# mrShark_09.net
KiCad netlist of a schematic drawn in EAGLE
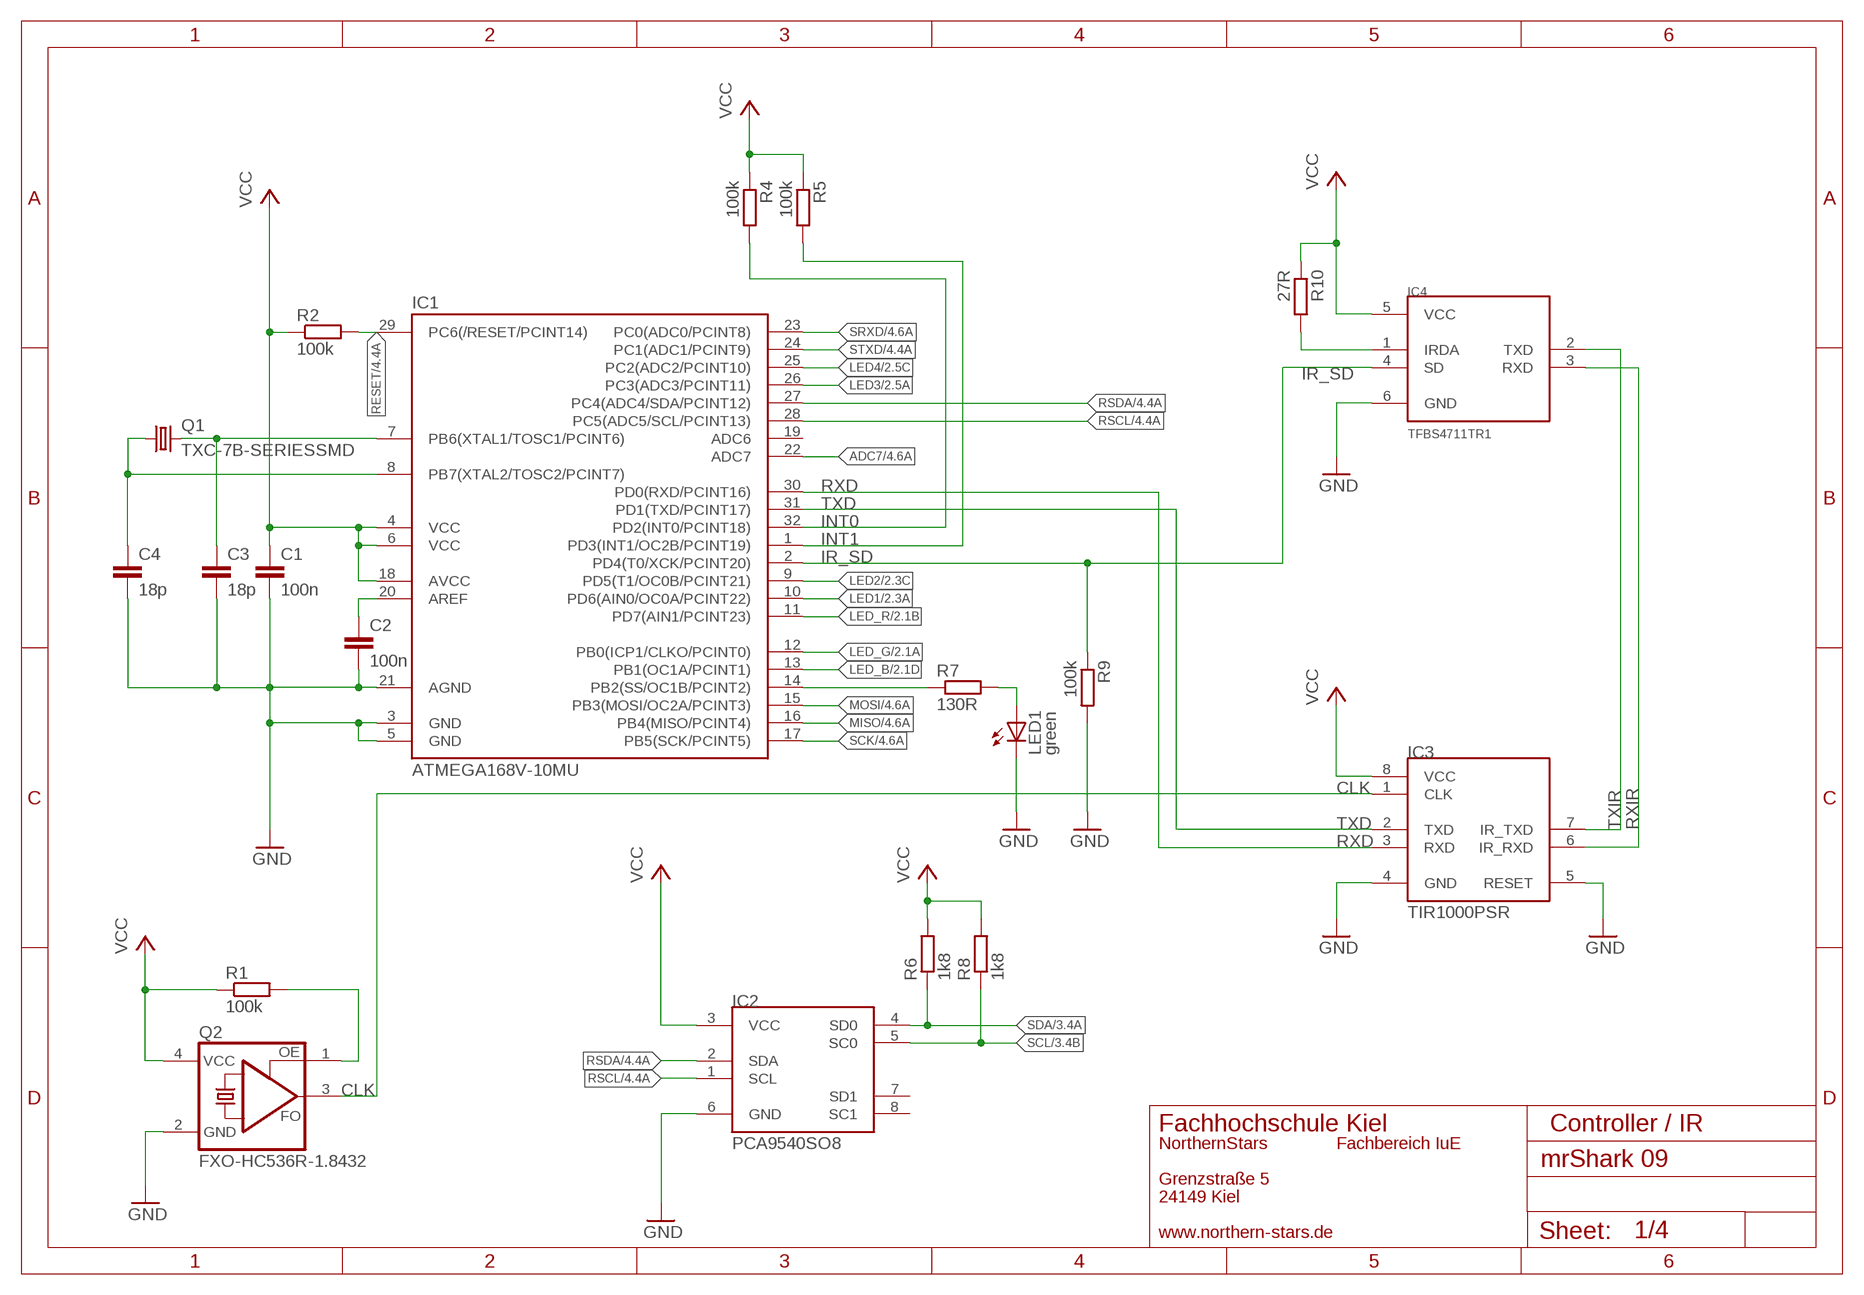
[diagram p0: schematic, sheet 1]
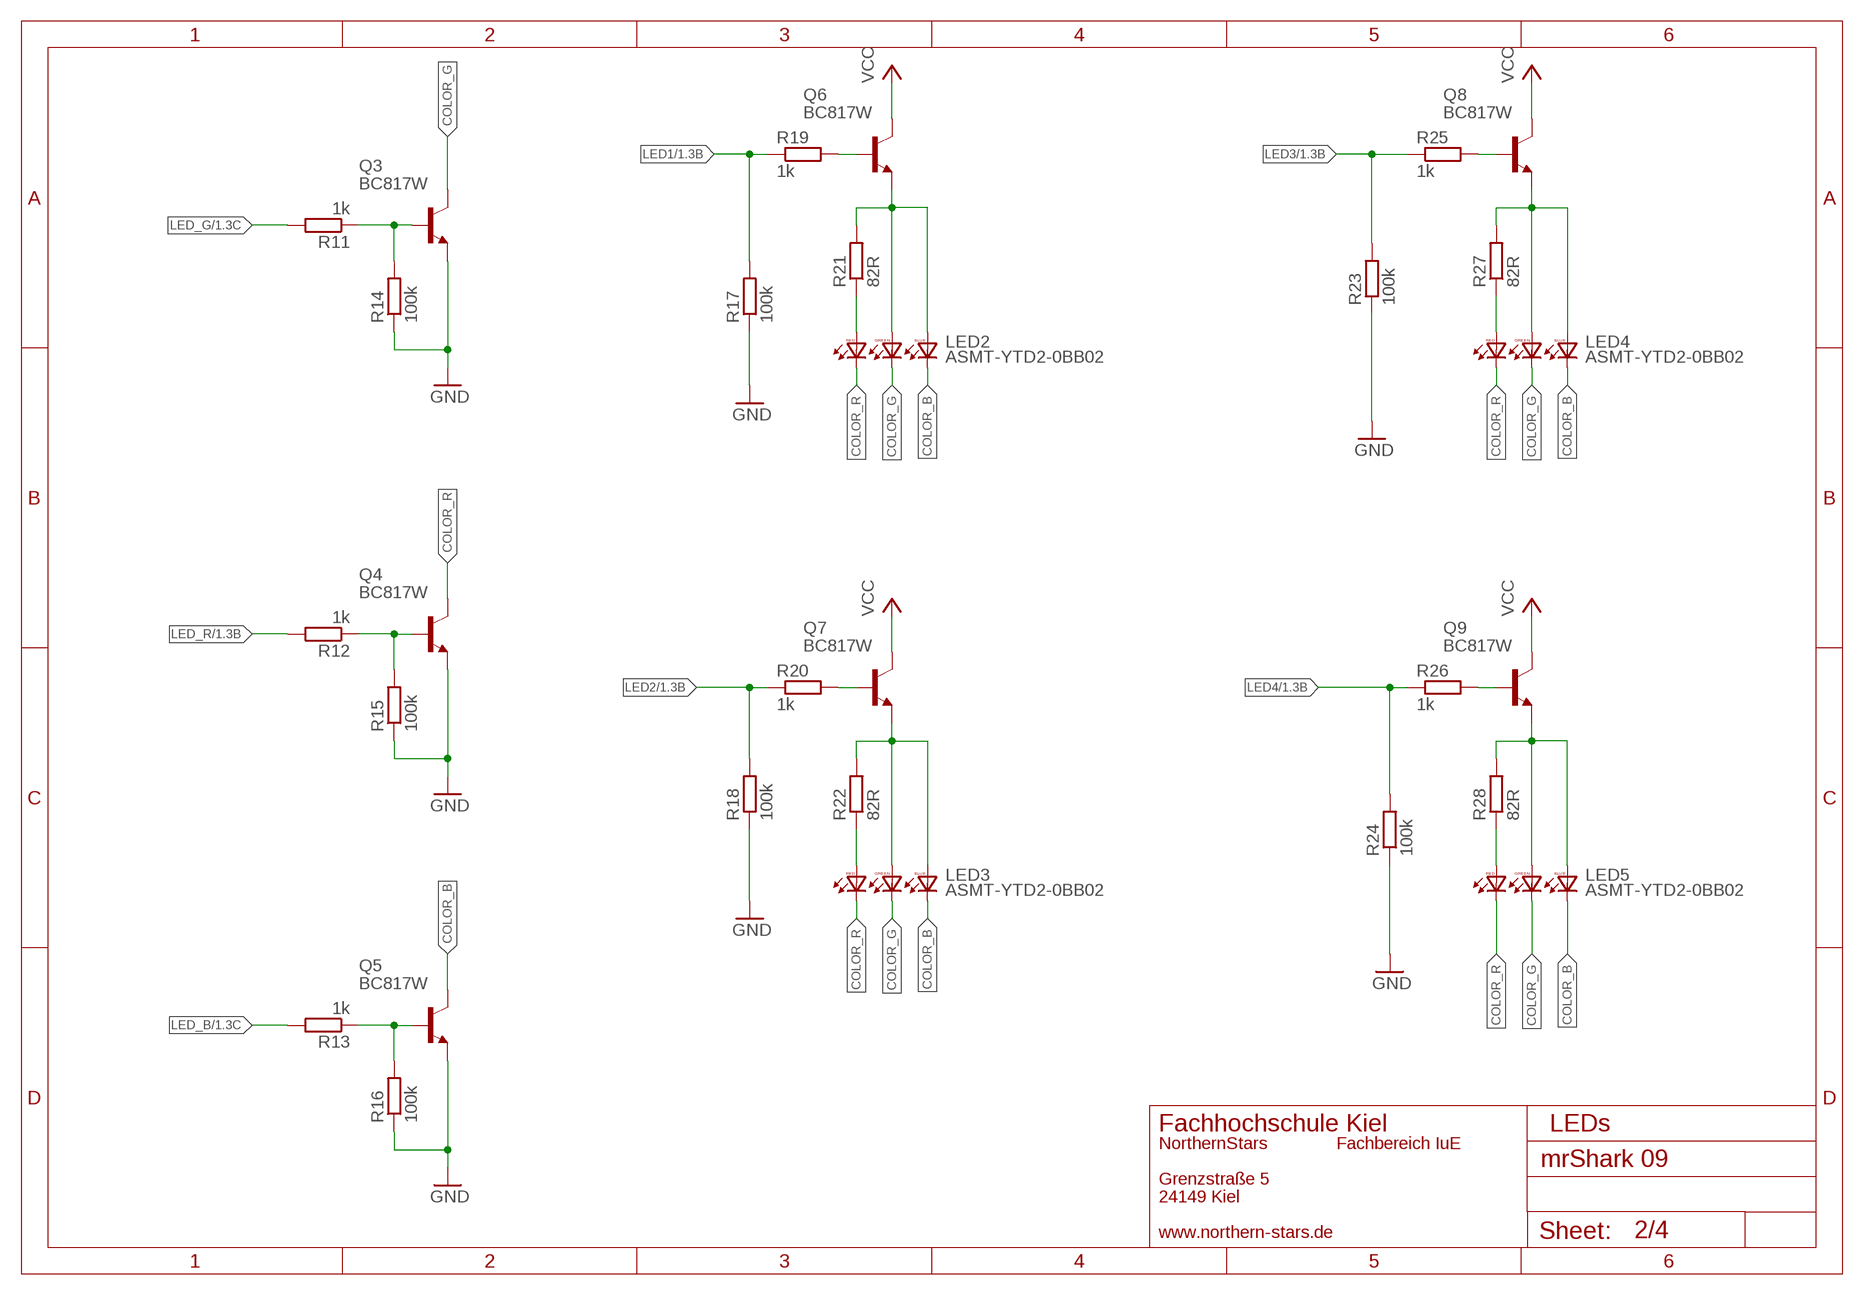
[diagram p1: schematic, sheet 2]
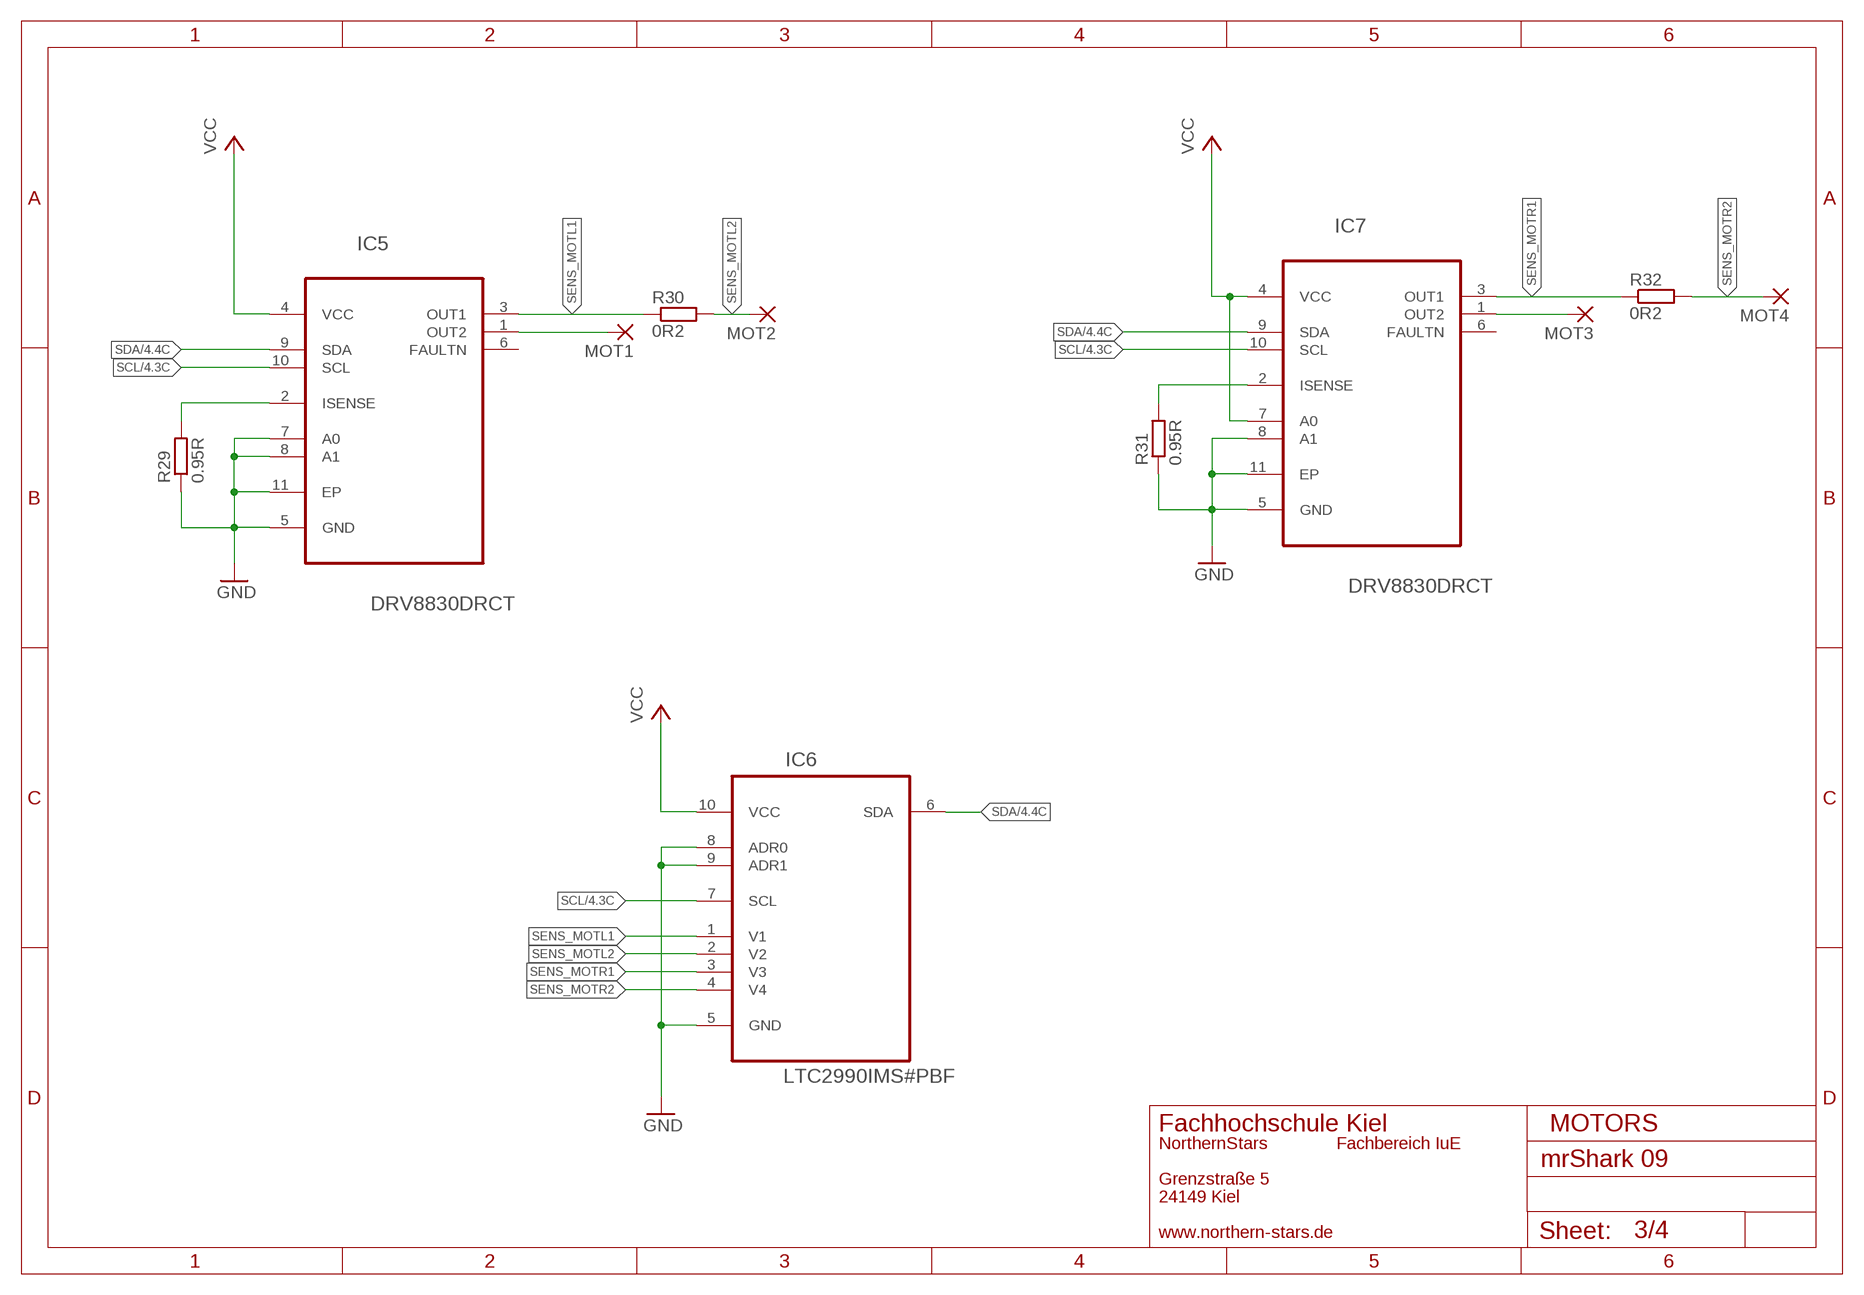
[diagram p2: schematic, sheet 3]
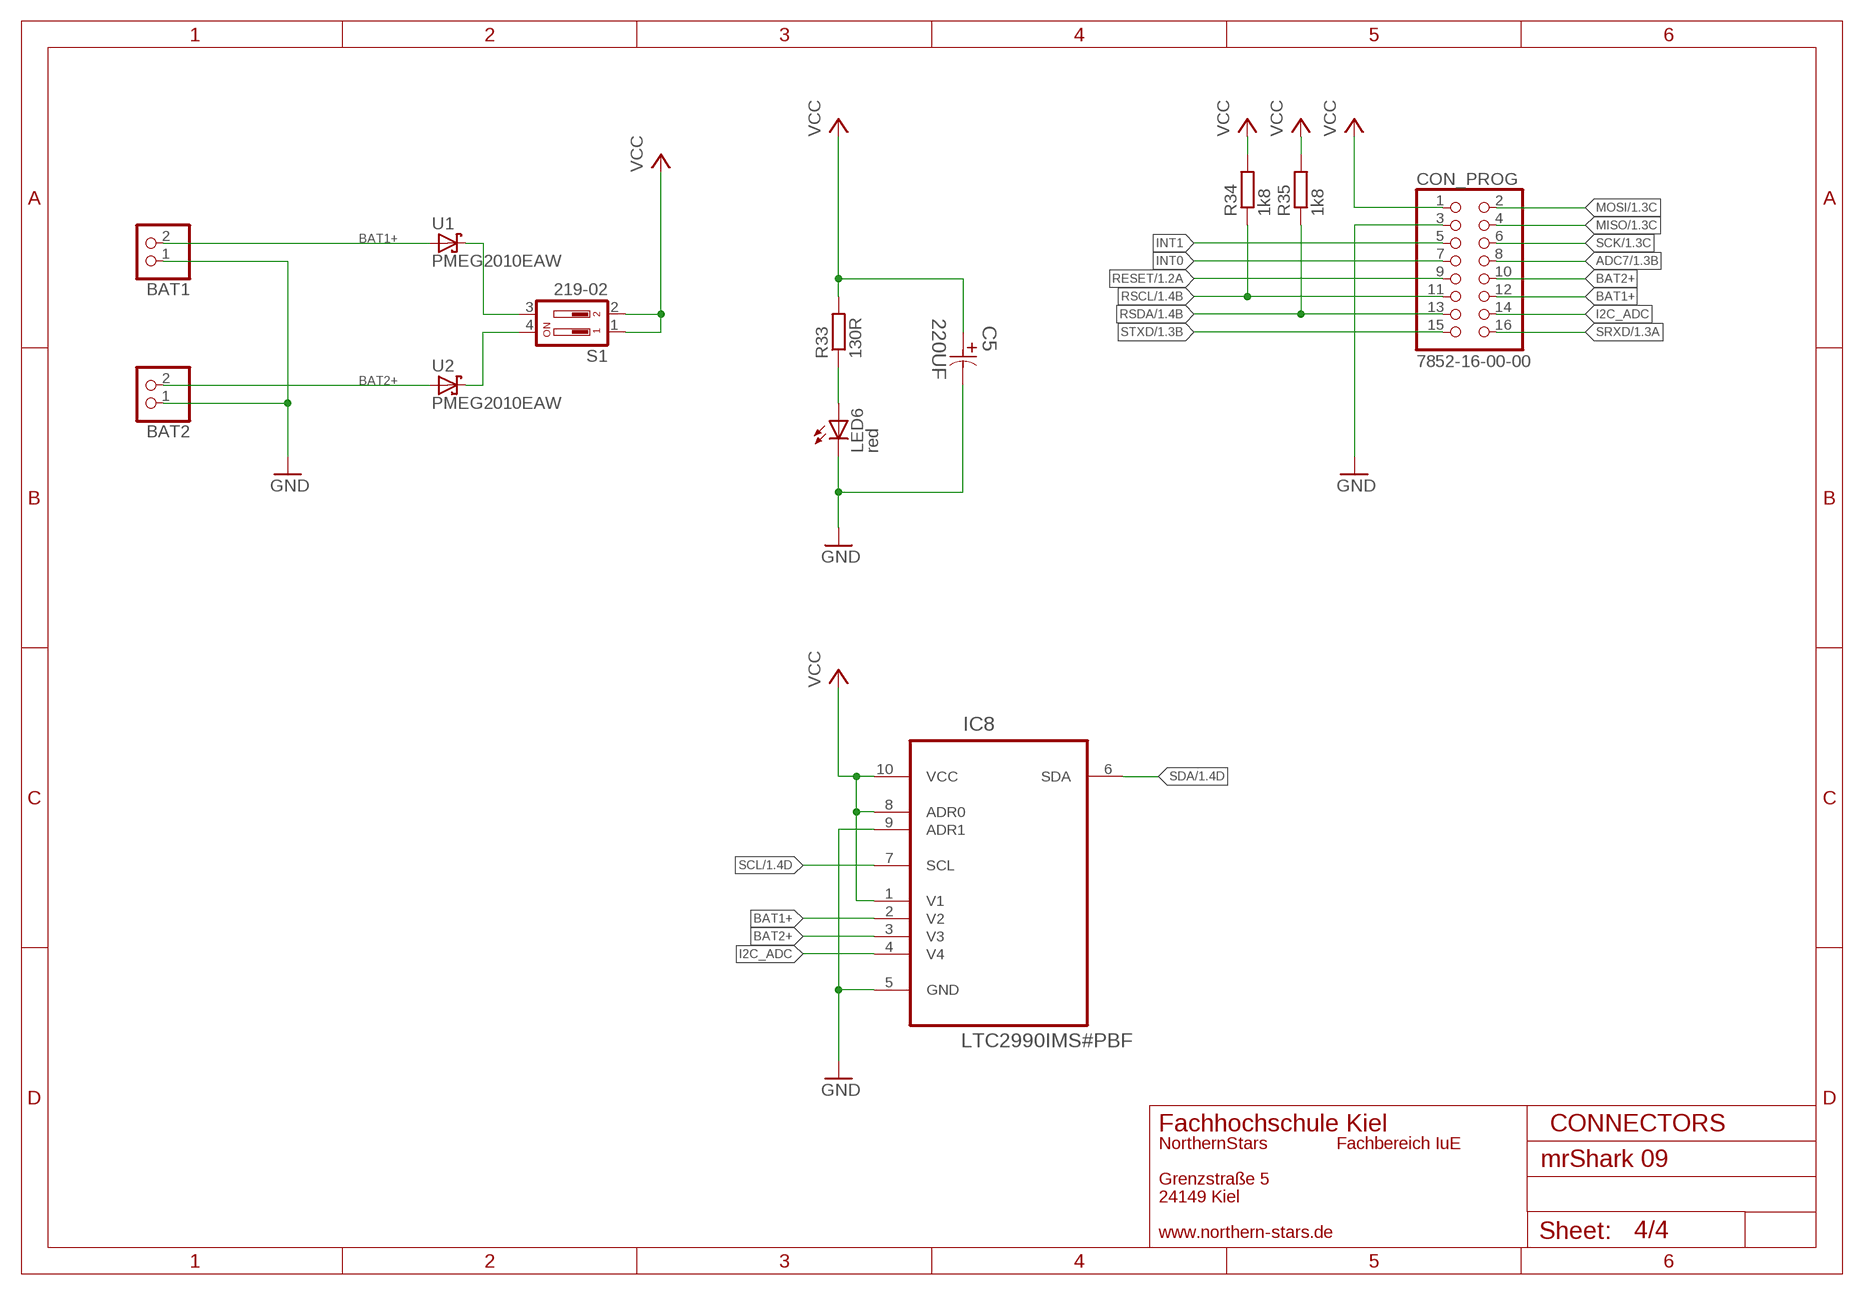
[diagram p3: schematic, sheet 4]

(export (version "E")
  (design (tool "Eeschema 10.0.6"))
  (components
    (comp (ref "BAT1")
      (value "PINHD-1X02_2.54-SMD")
      (footprint "eagle-import:1X02SMD")
      (libsource (lib "eagle-import") (part "PINHD-1X02_2.54-SMD"))
    )
    (comp (ref "BAT2")
      (value "PINHD-1X02_2.54-SMD")
      (footprint "eagle-import:1X02SMD")
      (libsource (lib "eagle-import") (part "PINHD-1X02_2.54-SMD"))
    )
    (comp (ref "C5")
      (value "220UF")
      (footprint "eagle-import:CAPAE660X800N")
      (fields (field (name "MPN") "EEE-FK1C221XP") (field (name "TOLERANCE") "±20 %"))
      (libsource (lib "eagle-import") (part "EEE--CASE-D8FK1C221XP"))
    )
    (comp (ref "CON_PROG")
      (value "7852-16-00-00")
      (footprint "eagle-import:2X08SMD")
      (libsource (lib "eagle-import") (part "PINHD-2X08_2.54-SMD"))
    )
    (comp (ref "IC8")
      (value "LTC2990IMS#PBF")
      (footprint "eagle-import:SOP50P490X110-10N")
      (libsource (lib "eagle-import") (part "LTC2990IMSPBF"))
    )
    (comp (ref "LED6")
      (value "red")
      (footprint "eagle-import:CHIPLED_0603")
      (libsource (lib "eagle-import") (part "LEDCHIPLED_0603"))
    )
    (comp (ref "R33")
      (value "130R")
      (footprint "eagle-import:R1206")
      (libsource (lib "eagle-import") (part "R-EU_R1206"))
    )
    (comp (ref "R34")
      (value "1k8")
      (footprint "eagle-import:R1206")
      (libsource (lib "eagle-import") (part "R-EU_R1206"))
    )
    (comp (ref "R35")
      (value "1k8")
      (footprint "eagle-import:R1206")
      (libsource (lib "eagle-import") (part "R-EU_R1206"))
    )
    (comp (ref "S1")
      (value "219-02")
      (footprint "eagle-import:CTS-219-02")
      (libsource (lib "eagle-import") (part "219-02"))
    )
    (comp (ref "U1")
      (value "PMEG2010EAW")
      (footprint "eagle-import:SOD323-W")
      (libsource (lib "eagle-import") (part "PMEG2010EAW"))
    )
    (comp (ref "U2")
      (value "PMEG2010EAW")
      (footprint "eagle-import:SOD323-W")
      (libsource (lib "eagle-import") (part "PMEG2010EAW"))
    )
    (comp (ref "LED2")
      (value "ASMT-YTD2-0BB02")
      (footprint "eagle-import:PLCC6K")
      (libsource (lib "eagle-import") (part "PLCC6K"))
    )
    (comp (ref "LED3")
      (value "ASMT-YTD2-0BB02")
      (footprint "eagle-import:PLCC6K")
      (libsource (lib "eagle-import") (part "PLCC6K"))
    )
    (comp (ref "LED4")
      (value "ASMT-YTD2-0BB02")
      (footprint "eagle-import:PLCC6K")
      (libsource (lib "eagle-import") (part "PLCC6K"))
    )
    (comp (ref "LED5")
      (value "ASMT-YTD2-0BB02")
      (footprint "eagle-import:PLCC6K")
      (libsource (lib "eagle-import") (part "PLCC6K"))
    )
    (comp (ref "Q3")
      (value "BC817W")
      (footprint "eagle-import:SOT323-BEC")
      (libsource (lib "eagle-import") (part "BC817W"))
    )
    (comp (ref "Q4")
      (value "BC817W")
      (footprint "eagle-import:SOT323-BEC")
      (libsource (lib "eagle-import") (part "BC817W"))
    )
    (comp (ref "Q5")
      (value "BC817W")
      (footprint "eagle-import:SOT323-BEC")
      (libsource (lib "eagle-import") (part "BC817W"))
    )
    (comp (ref "Q6")
      (value "BC817W")
      (footprint "eagle-import:SOT323-BEC")
      (libsource (lib "eagle-import") (part "BC817W"))
    )
    (comp (ref "Q7")
      (value "BC817W")
      (footprint "eagle-import:SOT323-BEC")
      (libsource (lib "eagle-import") (part "BC817W"))
    )
    (comp (ref "Q8")
      (value "BC817W")
      (footprint "eagle-import:SOT323-BEC")
      (libsource (lib "eagle-import") (part "BC817W"))
    )
    (comp (ref "Q9")
      (value "BC817W")
      (footprint "eagle-import:SOT323-BEC")
      (libsource (lib "eagle-import") (part "BC817W"))
    )
    (comp (ref "R11")
      (value "1k")
      (footprint "eagle-import:R1206")
      (libsource (lib "eagle-import") (part "R-EU_R1206"))
    )
    (comp (ref "R12")
      (value "1k")
      (footprint "eagle-import:R1206")
      (libsource (lib "eagle-import") (part "R-EU_R1206"))
    )
    (comp (ref "R13")
      (value "1k")
      (footprint "eagle-import:R1206")
      (libsource (lib "eagle-import") (part "R-EU_R1206"))
    )
    (comp (ref "R14")
      (value "100k")
      (footprint "eagle-import:R1206")
      (libsource (lib "eagle-import") (part "R-EU_R1206"))
    )
    (comp (ref "R15")
      (value "100k")
      (footprint "eagle-import:R1206")
      (libsource (lib "eagle-import") (part "R-EU_R1206"))
    )
    (comp (ref "R16")
      (value "100k")
      (footprint "eagle-import:R1206")
      (libsource (lib "eagle-import") (part "R-EU_R1206"))
    )
    (comp (ref "R17")
      (value "100k")
      (footprint "eagle-import:R1206")
      (libsource (lib "eagle-import") (part "R-EU_R1206"))
    )
    (comp (ref "R18")
      (value "100k")
      (footprint "eagle-import:R1206")
      (libsource (lib "eagle-import") (part "R-EU_R1206"))
    )
    (comp (ref "R19")
      (value "1k")
      (footprint "eagle-import:R1206")
      (libsource (lib "eagle-import") (part "R-EU_R1206"))
    )
    (comp (ref "R20")
      (value "1k")
      (footprint "eagle-import:R1206")
      (libsource (lib "eagle-import") (part "R-EU_R1206"))
    )
    (comp (ref "R21")
      (value "82R")
      (footprint "eagle-import:R1206")
      (libsource (lib "eagle-import") (part "R-EU_R1206"))
    )
    (comp (ref "R22")
      (value "82R")
      (footprint "eagle-import:R1206")
      (libsource (lib "eagle-import") (part "R-EU_R1206"))
    )
    (comp (ref "R23")
      (value "100k")
      (footprint "eagle-import:R1206")
      (libsource (lib "eagle-import") (part "R-EU_R1206"))
    )
    (comp (ref "R24")
      (value "100k")
      (footprint "eagle-import:R1206")
      (libsource (lib "eagle-import") (part "R-EU_R1206"))
    )
    (comp (ref "R25")
      (value "1k")
      (footprint "eagle-import:R1206")
      (libsource (lib "eagle-import") (part "R-EU_R1206"))
    )
    (comp (ref "R26")
      (value "1k")
      (footprint "eagle-import:R1206")
      (libsource (lib "eagle-import") (part "R-EU_R1206"))
    )
    (comp (ref "R27")
      (value "82R")
      (footprint "eagle-import:R1206")
      (libsource (lib "eagle-import") (part "R-EU_R1206"))
    )
    (comp (ref "R28")
      (value "82R")
      (footprint "eagle-import:R1206")
      (libsource (lib "eagle-import") (part "R-EU_R1206"))
    )
    (comp (ref "C1")
      (value "100n")
      (footprint "eagle-import:C1206")
      (libsource (lib "eagle-import") (part "C-EUC1206"))
    )
    (comp (ref "C2")
      (value "100n")
      (footprint "eagle-import:C1206")
      (libsource (lib "eagle-import") (part "C-EUC1206"))
    )
    (comp (ref "C3")
      (value "18p")
      (footprint "eagle-import:C0805")
      (libsource (lib "eagle-import") (part "C-EUC0805"))
    )
    (comp (ref "C4")
      (value "18p")
      (footprint "eagle-import:C0805")
      (libsource (lib "eagle-import") (part "C-EUC0805"))
    )
    (comp (ref "IC1")
      (value "ATMEGA168V-10MU")
      (footprint "eagle-import:TQFP32-08")
      (libsource (lib "eagle-import") (part "ATMEGA48/88/168-AU"))
    )
    (comp (ref "IC2")
      (value "PCA9540SO8")
      (footprint "eagle-import:SO8")
      (libsource (lib "eagle-import") (part "PCA9540SO8"))
    )
    (comp (ref "IC3")
      (value "TIR1000PSR")
      (footprint "eagle-import:SO-08")
      (libsource (lib "eagle-import") (part "TIR1000PSR"))
    )
    (comp (ref "IC4")
      (value "TFBS4711TR1")
      (footprint "eagle-import:TFBS4711")
      (libsource (lib "eagle-import") (part "TFBS4711TR1"))
    )
    (comp (ref "LED1")
      (value "green")
      (footprint "eagle-import:CHIPLED_0603")
      (libsource (lib "eagle-import") (part "LEDCHIPLED_0603"))
    )
    (comp (ref "Q1")
      (value "TXC-7B-SERIESSMD")
      (footprint "eagle-import:TXC_7B_SERIES")
      (libsource (lib "eagle-import") (part "TXC-7B-SERIESSMD"))
    )
    (comp (ref "Q2")
      (value "FXO-HC536R-1.8432")
      (footprint "eagle-import:HC536")
      (libsource (lib "eagle-import") (part "HC536R"))
    )
    (comp (ref "R1")
      (value "100k")
      (footprint "eagle-import:R1206")
      (libsource (lib "eagle-import") (part "R-EU_R1206"))
    )
    (comp (ref "R2")
      (value "100k")
      (footprint "eagle-import:R1206")
      (libsource (lib "eagle-import") (part "R-EU_R1206"))
    )
    (comp (ref "R4")
      (value "100k")
      (footprint "eagle-import:R1206")
      (libsource (lib "eagle-import") (part "R-EU_R1206"))
    )
    (comp (ref "R5")
      (value "100k")
      (footprint "eagle-import:R1206")
      (libsource (lib "eagle-import") (part "R-EU_R1206"))
    )
    (comp (ref "R6")
      (value "1k8")
      (footprint "eagle-import:R1206")
      (libsource (lib "eagle-import") (part "R-EU_R1206"))
    )
    (comp (ref "R7")
      (value "130R")
      (footprint "eagle-import:R1206")
      (libsource (lib "eagle-import") (part "R-EU_R1206"))
    )
    (comp (ref "R8")
      (value "1k8")
      (footprint "eagle-import:R1206")
      (libsource (lib "eagle-import") (part "R-EU_R1206"))
    )
    (comp (ref "R9")
      (value "100k")
      (footprint "eagle-import:R1206")
      (libsource (lib "eagle-import") (part "R-EU_R1206"))
    )
    (comp (ref "R10")
      (value "27R")
      (footprint "eagle-import:R1206")
      (libsource (lib "eagle-import") (part "R-EU_R1206"))
    )
    (comp (ref "IC5")
      (value "DRV8830DRCT")
      (footprint "eagle-import:SOP65P640X110-15N")
      (fields (field (name "MPN") "DRV8830DGQR"))
      (libsource (lib "eagle-import") (part "DRV8830DGQRMSOP"))
    )
    (comp (ref "IC6")
      (value "LTC2990IMS#PBF")
      (footprint "eagle-import:SOP50P490X110-10N")
      (libsource (lib "eagle-import") (part "LTC2990IMSPBF"))
    )
    (comp (ref "IC7")
      (value "DRV8830DRCT")
      (footprint "eagle-import:SOP65P640X110-15N")
      (fields (field (name "MPN") "DRV8830DGQR"))
      (libsource (lib "eagle-import") (part "DRV8830DGQRMSOP"))
    )
    (comp (ref "MOT1")
      (value "SMD5")
      (footprint "eagle-import:SMD2,54-5,08")
      (libsource (lib "eagle-import") (part "SMD5"))
    )
    (comp (ref "MOT2")
      (value "SMD5")
      (footprint "eagle-import:SMD2,54-5,08")
      (libsource (lib "eagle-import") (part "SMD5"))
    )
    (comp (ref "MOT3")
      (value "SMD5")
      (footprint "eagle-import:SMD2,54-5,08")
      (libsource (lib "eagle-import") (part "SMD5"))
    )
    (comp (ref "MOT4")
      (value "SMD5")
      (footprint "eagle-import:SMD2,54-5,08")
      (libsource (lib "eagle-import") (part "SMD5"))
    )
    (comp (ref "R29")
      (value "0.95R")
      (footprint "eagle-import:R1206")
      (libsource (lib "eagle-import") (part "R-EU_R1206"))
    )
    (comp (ref "R30")
      (value "0R2")
      (footprint "eagle-import:R1206")
      (libsource (lib "eagle-import") (part "R-EU_R1206"))
    )
    (comp (ref "R31")
      (value "0.95R")
      (footprint "eagle-import:R1206")
      (libsource (lib "eagle-import") (part "R-EU_R1206"))
    )
    (comp (ref "R32")
      (value "0R2")
      (footprint "eagle-import:R1206")
      (libsource (lib "eagle-import") (part "R-EU_R1206"))
    )
  )
  (nets
    (net (code "1") (name "ADC7") (class "Default")
      (node (ref "CON_PROG") (pin "8") (pinfunction "8_8") (pintype "passive"))
      (node (ref "IC1") (pin "22") (pinfunction "ADC7_22") (pintype "passive"))
    )
    (net (code "2") (name "BAT1+") (class "Default")
      (node (ref "BAT1") (pin "2") (pinfunction "2_2") (pintype "passive"))
      (node (ref "CON_PROG") (pin "12") (pinfunction "12_12") (pintype "passive"))
      (node (ref "IC8") (pin "2") (pinfunction "V2_2") (pintype "input"))
      (node (ref "U1") (pin "A") (pinfunction "A_A") (pintype "passive"))
    )
    (net (code "3") (name "BAT2+") (class "Default")
      (node (ref "BAT2") (pin "2") (pinfunction "2_2") (pintype "passive"))
      (node (ref "CON_PROG") (pin "10") (pinfunction "10_10") (pintype "passive"))
      (node (ref "IC8") (pin "3") (pinfunction "V3_3") (pintype "input"))
      (node (ref "U2") (pin "A") (pinfunction "A_A") (pintype "passive"))
    )
    (net (code "4") (name "CLK") (class "Default")
      (node (ref "IC3") (pin "1") (pinfunction "CLK_1") (pintype "bidirectional"))
      (node (ref "Q2") (pin "3") (pinfunction "FO_3") (pintype "output"))
    )
    (net (code "5") (name "COLOR_B") (class "Default")
      (node (ref "LED2") (pin "1") (pinfunction "BC_1") (pintype "passive"))
      (node (ref "LED3") (pin "1") (pinfunction "BC_1") (pintype "passive"))
      (node (ref "LED4") (pin "1") (pinfunction "BC_1") (pintype "passive"))
      (node (ref "LED5") (pin "1") (pinfunction "BC_1") (pintype "passive"))
      (node (ref "Q5") (pin "C") (pinfunction "C_C") (pintype "passive"))
    )
    (net (code "6") (name "COLOR_G") (class "Default")
      (node (ref "LED2") (pin "2") (pinfunction "GC_2") (pintype "passive"))
      (node (ref "LED3") (pin "2") (pinfunction "GC_2") (pintype "passive"))
      (node (ref "LED4") (pin "2") (pinfunction "GC_2") (pintype "passive"))
      (node (ref "LED5") (pin "2") (pinfunction "GC_2") (pintype "passive"))
      (node (ref "Q3") (pin "C") (pinfunction "C_C") (pintype "passive"))
    )
    (net (code "7") (name "COLOR_R") (class "Default")
      (node (ref "LED2") (pin "3") (pinfunction "RC_3") (pintype "passive"))
      (node (ref "LED3") (pin "3") (pinfunction "RC_3") (pintype "passive"))
      (node (ref "LED4") (pin "3") (pinfunction "RC_3") (pintype "passive"))
      (node (ref "LED5") (pin "3") (pinfunction "RC_3") (pintype "passive"))
      (node (ref "Q4") (pin "C") (pinfunction "C_C") (pintype "passive"))
    )
    (net (code "8") (name "GND") (class "Default")
      (node (ref "BAT1") (pin "1") (pinfunction "1_1") (pintype "passive"))
      (node (ref "BAT2") (pin "1") (pinfunction "1_1") (pintype "passive"))
      (node (ref "C1") (pin "2") (pinfunction "2_2") (pintype "passive"))
      (node (ref "C2") (pin "2") (pinfunction "2_2") (pintype "passive"))
      (node (ref "C3") (pin "2") (pinfunction "2_2") (pintype "passive"))
      (node (ref "C4") (pin "2") (pinfunction "2_2") (pintype "passive"))
      (node (ref "C5") (pin "2") (pinfunction "2_2") (pintype "passive"))
      (node (ref "CON_PROG") (pin "3") (pinfunction "3_3") (pintype "passive"))
      (node (ref "IC1") (pin "21") (pinfunction "AGND_21") (pintype "power_in"))
      (node (ref "IC1") (pin "3") (pinfunction "GND_3") (pintype "power_in"))
      (node (ref "IC1") (pin "5") (pinfunction "GND_5") (pintype "power_in"))
      (node (ref "IC2") (pin "6") (pinfunction "GND_6") (pintype "bidirectional"))
      (node (ref "IC3") (pin "4") (pinfunction "GND_4") (pintype "bidirectional"))
      (node (ref "IC3") (pin "5") (pinfunction "RESET_5") (pintype "bidirectional"))
      (node (ref "IC4") (pin "6") (pinfunction "GND_6") (pintype "bidirectional"))
      (node (ref "IC5") (pin "11") (pinfunction "EP_11") (pintype "passive"))
      (node (ref "IC5") (pin "5") (pinfunction "GND_5") (pintype "passive"))
      (node (ref "IC5") (pin "7") (pinfunction "A0_7") (pintype "input"))
      (node (ref "IC5") (pin "8") (pinfunction "A1_8") (pintype "input"))
      (node (ref "IC6") (pin "5") (pinfunction "GND_5") (pintype "passive"))
      (node (ref "IC6") (pin "8") (pinfunction "ADR0_8") (pintype "input"))
      (node (ref "IC6") (pin "9") (pinfunction "ADR1_9") (pintype "input"))
      (node (ref "IC7") (pin "11") (pinfunction "EP_11") (pintype "passive"))
      (node (ref "IC7") (pin "5") (pinfunction "GND_5") (pintype "passive"))
      (node (ref "IC7") (pin "8") (pinfunction "A1_8") (pintype "input"))
      (node (ref "IC8") (pin "5") (pinfunction "GND_5") (pintype "passive"))
      (node (ref "IC8") (pin "9") (pinfunction "ADR1_9") (pintype "input"))
      (node (ref "LED1") (pin "C") (pinfunction "C_C") (pintype "passive"))
      (node (ref "LED6") (pin "C") (pinfunction "C_C") (pintype "passive"))
      (node (ref "Q2") (pin "2") (pinfunction "GND_2") (pintype "power_in"))
      (node (ref "Q3") (pin "E") (pinfunction "E_E") (pintype "passive"))
      (node (ref "Q4") (pin "E") (pinfunction "E_E") (pintype "passive"))
      (node (ref "Q5") (pin "E") (pinfunction "E_E") (pintype "passive"))
      (node (ref "R14") (pin "1") (pinfunction "1_1") (pintype "passive"))
      (node (ref "R15") (pin "1") (pinfunction "1_1") (pintype "passive"))
      (node (ref "R16") (pin "1") (pinfunction "1_1") (pintype "passive"))
      (node (ref "R17") (pin "1") (pinfunction "1_1") (pintype "passive"))
      (node (ref "R18") (pin "1") (pinfunction "1_1") (pintype "passive"))
      (node (ref "R23") (pin "1") (pinfunction "1_1") (pintype "passive"))
      (node (ref "R24") (pin "1") (pinfunction "1_1") (pintype "passive"))
      (node (ref "R29") (pin "1") (pinfunction "1_1") (pintype "passive"))
      (node (ref "R31") (pin "1") (pinfunction "1_1") (pintype "passive"))
      (node (ref "R9") (pin "2") (pinfunction "2_2") (pintype "passive"))
    )
    (net (code "9") (name "I2C_ADC") (class "Default")
      (node (ref "CON_PROG") (pin "14") (pinfunction "14_14") (pintype "passive"))
      (node (ref "IC8") (pin "4") (pinfunction "V4_4") (pintype "input"))
    )
    (net (code "10") (name "INT0") (class "Default")
      (node (ref "CON_PROG") (pin "7") (pinfunction "7_7") (pintype "passive"))
      (node (ref "IC1") (pin "32") (pinfunction "PD2(INT0/PCINT18)_32") (pintype "bidirectional"))
      (node (ref "R4") (pin "2") (pinfunction "2_2") (pintype "passive"))
    )
    (net (code "11") (name "INT1") (class "Default")
      (node (ref "CON_PROG") (pin "5") (pinfunction "5_5") (pintype "passive"))
      (node (ref "IC1") (pin "1") (pinfunction "PD3(INT1/OC2B/PCINT19)_1") (pintype "bidirectional"))
      (node (ref "R5") (pin "2") (pinfunction "2_2") (pintype "passive"))
    )
    (net (code "12") (name "IR_SD") (class "Default")
      (node (ref "IC1") (pin "2") (pinfunction "PD4(T0/XCK/PCINT20)_2") (pintype "bidirectional"))
      (node (ref "IC4") (pin "4") (pinfunction "SD_4") (pintype "bidirectional"))
      (node (ref "R9") (pin "1") (pinfunction "1_1") (pintype "passive"))
    )
    (net (code "13") (name "LED1") (class "Default")
      (node (ref "IC1") (pin "10") (pinfunction "PD6(AIN0/OC0A/PCINT22)_10") (pintype "bidirectional"))
      (node (ref "R17") (pin "2") (pinfunction "2_2") (pintype "passive"))
      (node (ref "R19") (pin "1") (pinfunction "1_1") (pintype "passive"))
    )
    (net (code "14") (name "LED2") (class "Default")
      (node (ref "IC1") (pin "9") (pinfunction "PD5(T1/OC0B/PCINT21)_9") (pintype "bidirectional"))
      (node (ref "R18") (pin "2") (pinfunction "2_2") (pintype "passive"))
      (node (ref "R20") (pin "1") (pinfunction "1_1") (pintype "passive"))
    )
    (net (code "15") (name "LED3") (class "Default")
      (node (ref "IC1") (pin "26") (pinfunction "PC3(ADC3/PCINT11)_26") (pintype "bidirectional"))
      (node (ref "R23") (pin "2") (pinfunction "2_2") (pintype "passive"))
      (node (ref "R25") (pin "1") (pinfunction "1_1") (pintype "passive"))
    )
    (net (code "16") (name "LED4") (class "Default")
      (node (ref "IC1") (pin "25") (pinfunction "PC2(ADC2/PCINT10)_25") (pintype "bidirectional"))
      (node (ref "R24") (pin "2") (pinfunction "2_2") (pintype "passive"))
      (node (ref "R26") (pin "1") (pinfunction "1_1") (pintype "passive"))
    )
    (net (code "17") (name "LED_B") (class "Default")
      (node (ref "IC1") (pin "13") (pinfunction "PB1(OC1A/PCINT1)_13") (pintype "bidirectional"))
      (node (ref "R13") (pin "2") (pinfunction "2_2") (pintype "passive"))
    )
    (net (code "18") (name "LED_G") (class "Default")
      (node (ref "IC1") (pin "12") (pinfunction "PB0(ICP1/CLKO/PCINT0)_12") (pintype "bidirectional"))
      (node (ref "R11") (pin "2") (pinfunction "2_2") (pintype "passive"))
    )
    (net (code "19") (name "LED_R") (class "Default")
      (node (ref "IC1") (pin "11") (pinfunction "PD7(AIN1/PCINT23)_11") (pintype "bidirectional"))
      (node (ref "R12") (pin "2") (pinfunction "2_2") (pintype "passive"))
    )
    (net (code "20") (name "MISO") (class "Default")
      (node (ref "CON_PROG") (pin "4") (pinfunction "4_4") (pintype "passive"))
      (node (ref "IC1") (pin "16") (pinfunction "PB4(MISO/PCINT4)_16") (pintype "bidirectional"))
    )
    (net (code "21") (name "MOSI") (class "Default")
      (node (ref "CON_PROG") (pin "2") (pinfunction "2_2") (pintype "passive"))
      (node (ref "IC1") (pin "15") (pinfunction "PB3(MOSI/OC2A/PCINT3)_15") (pintype "bidirectional"))
    )
    (net (code "22") (name "Net-(IC1-AREF)") (class "Default")
      (node (ref "C2") (pin "1") (pinfunction "1_1") (pintype "passive"))
      (node (ref "IC1") (pin "20") (pinfunction "AREF_20") (pintype "passive"))
    )
    (net (code "23") (name "Net-(IC1-PB2(SS{slash}OC1B{slash}PCINT2))") (class "Default")
      (node (ref "IC1") (pin "14") (pinfunction "PB2(SS/OC1B/PCINT2)_14") (pintype "bidirectional"))
      (node (ref "R7") (pin "1") (pinfunction "1_1") (pintype "passive"))
    )
    (net (code "24") (name "Net-(IC1-PB6(XTAL1{slash}TOSC1{slash}PCINT6))") (class "Default")
      (node (ref "C3") (pin "1") (pinfunction "1_1") (pintype "passive"))
      (node (ref "IC1") (pin "7") (pinfunction "PB6(XTAL1/TOSC1/PCINT6)_7") (pintype "bidirectional"))
      (node (ref "Q1") (pin "3") (pinfunction "2_3") (pintype "passive"))
    )
    (net (code "25") (name "Net-(IC1-PB7(XTAL2{slash}TOSC2{slash}PCINT7))") (class "Default")
      (node (ref "C4") (pin "1") (pinfunction "1_1") (pintype "passive"))
      (node (ref "IC1") (pin "8") (pinfunction "PB7(XTAL2/TOSC2/PCINT7)_8") (pintype "bidirectional"))
      (node (ref "Q1") (pin "1") (pinfunction "1_1") (pintype "passive"))
    )
    (net (code "26") (name "Net-(IC4-IRDA)") (class "Default")
      (node (ref "IC4") (pin "1") (pinfunction "IRDA_1") (pintype "bidirectional"))
      (node (ref "R10") (pin "2") (pinfunction "2_2") (pintype "passive"))
    )
    (net (code "27") (name "Net-(IC5-ISENSE)") (class "Default")
      (node (ref "IC5") (pin "2") (pinfunction "ISENSE_2") (pintype "input"))
      (node (ref "R29") (pin "2") (pinfunction "2_2") (pintype "passive"))
    )
    (net (code "28") (name "Net-(IC5-OUT2)") (class "Default")
      (node (ref "IC5") (pin "1") (pinfunction "OUT2_1") (pintype "output"))
      (node (ref "MOT1") (pin "1") (pinfunction "P_1") (pintype "passive"))
    )
    (net (code "29") (name "Net-(IC7-ISENSE)") (class "Default")
      (node (ref "IC7") (pin "2") (pinfunction "ISENSE_2") (pintype "input"))
      (node (ref "R31") (pin "2") (pinfunction "2_2") (pintype "passive"))
    )
    (net (code "30") (name "Net-(IC7-OUT2)") (class "Default")
      (node (ref "IC7") (pin "1") (pinfunction "OUT2_1") (pintype "output"))
      (node (ref "MOT3") (pin "1") (pinfunction "P_1") (pintype "passive"))
    )
    (net (code "31") (name "Net-(LED1-PadA)") (class "Default")
      (node (ref "LED1") (pin "A") (pinfunction "A_A") (pintype "passive"))
      (node (ref "R7") (pin "2") (pinfunction "2_2") (pintype "passive"))
    )
    (net (code "32") (name "Net-(LED2-BA)") (class "Default")
      (node (ref "LED2") (pin "5") (pinfunction "GA_5") (pintype "passive"))
      (node (ref "LED2") (pin "6") (pinfunction "BA_6") (pintype "passive"))
      (node (ref "Q6") (pin "E") (pinfunction "E_E") (pintype "passive"))
      (node (ref "R21") (pin "2") (pinfunction "2_2") (pintype "passive"))
    )
    (net (code "33") (name "Net-(LED2-RA)") (class "Default")
      (node (ref "LED2") (pin "4") (pinfunction "RA_4") (pintype "passive"))
      (node (ref "R21") (pin "1") (pinfunction "1_1") (pintype "passive"))
    )
    (net (code "34") (name "Net-(LED3-BA)") (class "Default")
      (node (ref "LED3") (pin "5") (pinfunction "GA_5") (pintype "passive"))
      (node (ref "LED3") (pin "6") (pinfunction "BA_6") (pintype "passive"))
      (node (ref "Q7") (pin "E") (pinfunction "E_E") (pintype "passive"))
      (node (ref "R22") (pin "2") (pinfunction "2_2") (pintype "passive"))
    )
    (net (code "35") (name "Net-(LED3-RA)") (class "Default")
      (node (ref "LED3") (pin "4") (pinfunction "RA_4") (pintype "passive"))
      (node (ref "R22") (pin "1") (pinfunction "1_1") (pintype "passive"))
    )
    (net (code "36") (name "Net-(LED4-BA)") (class "Default")
      (node (ref "LED4") (pin "5") (pinfunction "GA_5") (pintype "passive"))
      (node (ref "LED4") (pin "6") (pinfunction "BA_6") (pintype "passive"))
      (node (ref "Q8") (pin "E") (pinfunction "E_E") (pintype "passive"))
      (node (ref "R27") (pin "2") (pinfunction "2_2") (pintype "passive"))
    )
    (net (code "37") (name "Net-(LED4-RA)") (class "Default")
      (node (ref "LED4") (pin "4") (pinfunction "RA_4") (pintype "passive"))
      (node (ref "R27") (pin "1") (pinfunction "1_1") (pintype "passive"))
    )
    (net (code "38") (name "Net-(LED5-BA)") (class "Default")
      (node (ref "LED5") (pin "5") (pinfunction "GA_5") (pintype "passive"))
      (node (ref "LED5") (pin "6") (pinfunction "BA_6") (pintype "passive"))
      (node (ref "Q9") (pin "E") (pinfunction "E_E") (pintype "passive"))
      (node (ref "R28") (pin "2") (pinfunction "2_2") (pintype "passive"))
    )
    (net (code "39") (name "Net-(LED5-RA)") (class "Default")
      (node (ref "LED5") (pin "4") (pinfunction "RA_4") (pintype "passive"))
      (node (ref "R28") (pin "1") (pinfunction "1_1") (pintype "passive"))
    )
    (net (code "40") (name "Net-(LED6-PadA)") (class "Default")
      (node (ref "LED6") (pin "A") (pinfunction "A_A") (pintype "passive"))
      (node (ref "R33") (pin "1") (pinfunction "1_1") (pintype "passive"))
    )
    (net (code "41") (name "Net-(Q2-OE)") (class "Default")
      (node (ref "Q2") (pin "1") (pinfunction "OE_1") (pintype "input"))
      (node (ref "R1") (pin "2") (pinfunction "2_2") (pintype "passive"))
    )
    (net (code "42") (name "Net-(Q3-PadB)") (class "Default")
      (node (ref "Q3") (pin "B") (pinfunction "B_B") (pintype "passive"))
      (node (ref "R11") (pin "1") (pinfunction "1_1") (pintype "passive"))
      (node (ref "R14") (pin "2") (pinfunction "2_2") (pintype "passive"))
    )
    (net (code "43") (name "Net-(Q4-PadB)") (class "Default")
      (node (ref "Q4") (pin "B") (pinfunction "B_B") (pintype "passive"))
      (node (ref "R12") (pin "1") (pinfunction "1_1") (pintype "passive"))
      (node (ref "R15") (pin "2") (pinfunction "2_2") (pintype "passive"))
    )
    (net (code "44") (name "Net-(Q5-PadB)") (class "Default")
      (node (ref "Q5") (pin "B") (pinfunction "B_B") (pintype "passive"))
      (node (ref "R13") (pin "1") (pinfunction "1_1") (pintype "passive"))
      (node (ref "R16") (pin "2") (pinfunction "2_2") (pintype "passive"))
    )
    (net (code "45") (name "Net-(Q6-PadB)") (class "Default")
      (node (ref "Q6") (pin "B") (pinfunction "B_B") (pintype "passive"))
      (node (ref "R19") (pin "2") (pinfunction "2_2") (pintype "passive"))
    )
    (net (code "46") (name "Net-(Q7-PadB)") (class "Default")
      (node (ref "Q7") (pin "B") (pinfunction "B_B") (pintype "passive"))
      (node (ref "R20") (pin "2") (pinfunction "2_2") (pintype "passive"))
    )
    (net (code "47") (name "Net-(Q8-PadB)") (class "Default")
      (node (ref "Q8") (pin "B") (pinfunction "B_B") (pintype "passive"))
      (node (ref "R25") (pin "2") (pinfunction "2_2") (pintype "passive"))
    )
    (net (code "48") (name "Net-(Q9-PadB)") (class "Default")
      (node (ref "Q9") (pin "B") (pinfunction "B_B") (pintype "passive"))
      (node (ref "R26") (pin "2") (pinfunction "2_2") (pintype "passive"))
    )
    (net (code "49") (name "Net-(S1-Pad3)") (class "Default")
      (node (ref "S1") (pin "3") (pinfunction "3_3") (pintype "passive"))
      (node (ref "U1") (pin "C") (pinfunction "C_C") (pintype "passive"))
    )
    (net (code "50") (name "Net-(S1-Pad4)") (class "Default")
      (node (ref "S1") (pin "4") (pinfunction "4_4") (pintype "passive"))
      (node (ref "U2") (pin "C") (pinfunction "C_C") (pintype "passive"))
    )
    (net (code "51") (name "RESET") (class "Default")
      (node (ref "CON_PROG") (pin "9") (pinfunction "9_9") (pintype "passive"))
      (node (ref "IC1") (pin "29") (pinfunction "PC6(/RESET/PCINT14)_29") (pintype "bidirectional"))
      (node (ref "R2") (pin "2") (pinfunction "2_2") (pintype "passive"))
    )
    (net (code "52") (name "RSCL") (class "Default")
      (node (ref "CON_PROG") (pin "11") (pinfunction "11_11") (pintype "passive"))
      (node (ref "IC1") (pin "28") (pinfunction "PC5(ADC5/SCL/PCINT13)_28") (pintype "bidirectional"))
      (node (ref "IC2") (pin "1") (pinfunction "SCL_1") (pintype "bidirectional"))
      (node (ref "R34") (pin "1") (pinfunction "1_1") (pintype "passive"))
    )
    (net (code "53") (name "RSDA") (class "Default")
      (node (ref "CON_PROG") (pin "13") (pinfunction "13_13") (pintype "passive"))
      (node (ref "IC1") (pin "27") (pinfunction "PC4(ADC4/SDA/PCINT12)_27") (pintype "bidirectional"))
      (node (ref "IC2") (pin "2") (pinfunction "SDA_2") (pintype "bidirectional"))
      (node (ref "R35") (pin "1") (pinfunction "1_1") (pintype "passive"))
    )
    (net (code "54") (name "RXD") (class "Default")
      (node (ref "IC1") (pin "30") (pinfunction "PD0(RXD/PCINT16)_30") (pintype "bidirectional"))
      (node (ref "IC3") (pin "3") (pinfunction "RXD_3") (pintype "bidirectional"))
    )
    (net (code "55") (name "RXIR") (class "Default")
      (node (ref "IC3") (pin "6") (pinfunction "IR_RXD_6") (pintype "bidirectional"))
      (node (ref "IC4") (pin "3") (pinfunction "RXD_3") (pintype "output"))
    )
    (net (code "56") (name "SCK") (class "Default")
      (node (ref "CON_PROG") (pin "6") (pinfunction "6_6") (pintype "passive"))
      (node (ref "IC1") (pin "17") (pinfunction "PB5(SCK/PCINT5)_17") (pintype "bidirectional"))
    )
    (net (code "57") (name "SCL") (class "Default")
      (node (ref "IC2") (pin "5") (pinfunction "SC0_5") (pintype "bidirectional"))
      (node (ref "IC5") (pin "10") (pinfunction "SCL_10") (pintype "input"))
      (node (ref "IC6") (pin "7") (pinfunction "SCL_7") (pintype "input"))
      (node (ref "IC7") (pin "10") (pinfunction "SCL_10") (pintype "input"))
      (node (ref "IC8") (pin "7") (pinfunction "SCL_7") (pintype "input"))
      (node (ref "R8") (pin "1") (pinfunction "1_1") (pintype "passive"))
    )
    (net (code "58") (name "SDA") (class "Default")
      (node (ref "IC2") (pin "4") (pinfunction "SD0_4") (pintype "bidirectional"))
      (node (ref "IC5") (pin "9") (pinfunction "SDA_9") (pintype "bidirectional"))
      (node (ref "IC6") (pin "6") (pinfunction "SDA_6") (pintype "bidirectional"))
      (node (ref "IC7") (pin "9") (pinfunction "SDA_9") (pintype "bidirectional"))
      (node (ref "IC8") (pin "6") (pinfunction "SDA_6") (pintype "bidirectional"))
      (node (ref "R6") (pin "1") (pinfunction "1_1") (pintype "passive"))
    )
    (net (code "59") (name "SENS_MOTL1") (class "Default")
      (node (ref "IC5") (pin "3") (pinfunction "OUT1_3") (pintype "output"))
      (node (ref "IC6") (pin "1") (pinfunction "V1_1") (pintype "input"))
      (node (ref "R30") (pin "1") (pinfunction "1_1") (pintype "passive"))
    )
    (net (code "60") (name "SENS_MOTL2") (class "Default")
      (node (ref "IC6") (pin "2") (pinfunction "V2_2") (pintype "input"))
      (node (ref "MOT2") (pin "1") (pinfunction "P_1") (pintype "passive"))
      (node (ref "R30") (pin "2") (pinfunction "2_2") (pintype "passive"))
    )
    (net (code "61") (name "SENS_MOTR1") (class "Default")
      (node (ref "IC6") (pin "3") (pinfunction "V3_3") (pintype "input"))
      (node (ref "IC7") (pin "3") (pinfunction "OUT1_3") (pintype "output"))
      (node (ref "R32") (pin "1") (pinfunction "1_1") (pintype "passive"))
    )
    (net (code "62") (name "SENS_MOTR2") (class "Default")
      (node (ref "IC6") (pin "4") (pinfunction "V4_4") (pintype "input"))
      (node (ref "MOT4") (pin "1") (pinfunction "P_1") (pintype "passive"))
      (node (ref "R32") (pin "2") (pinfunction "2_2") (pintype "passive"))
    )
    (net (code "63") (name "SRXD") (class "Default")
      (node (ref "CON_PROG") (pin "16") (pinfunction "16_16") (pintype "passive"))
      (node (ref "IC1") (pin "23") (pinfunction "PC0(ADC0/PCINT8)_23") (pintype "bidirectional"))
    )
    (net (code "64") (name "STXD") (class "Default")
      (node (ref "CON_PROG") (pin "15") (pinfunction "15_15") (pintype "passive"))
      (node (ref "IC1") (pin "24") (pinfunction "PC1(ADC1/PCINT9)_24") (pintype "bidirectional"))
    )
    (net (code "65") (name "TXD") (class "Default")
      (node (ref "IC1") (pin "31") (pinfunction "PD1(TXD/PCINT17)_31") (pintype "bidirectional"))
      (node (ref "IC3") (pin "2") (pinfunction "TXD_2") (pintype "bidirectional"))
    )
    (net (code "66") (name "TXIR") (class "Default")
      (node (ref "IC3") (pin "7") (pinfunction "IR_TXD_7") (pintype "bidirectional"))
      (node (ref "IC4") (pin "2") (pinfunction "TXD_2") (pintype "input"))
    )
    (net (code "67") (name "VCC") (class "Default")
      (node (ref "C1") (pin "1") (pinfunction "1_1") (pintype "passive"))
      (node (ref "C5") (pin "1") (pinfunction "1_1") (pintype "passive"))
      (node (ref "CON_PROG") (pin "1") (pinfunction "1_1") (pintype "passive"))
      (node (ref "IC1") (pin "18") (pinfunction "AVCC_18") (pintype "passive"))
      (node (ref "IC1") (pin "4") (pinfunction "VCC_4") (pintype "power_in"))
      (node (ref "IC1") (pin "6") (pinfunction "VCC_6") (pintype "power_in"))
      (node (ref "IC2") (pin "3") (pinfunction "VCC_3") (pintype "bidirectional"))
      (node (ref "IC3") (pin "8") (pinfunction "VCC_8") (pintype "bidirectional"))
      (node (ref "IC4") (pin "5") (pinfunction "VCC_5") (pintype "power_in"))
      (node (ref "IC5") (pin "4") (pinfunction "VCC_4") (pintype "power_in"))
      (node (ref "IC6") (pin "10") (pinfunction "VCC_10") (pintype "power_in"))
      (node (ref "IC7") (pin "4") (pinfunction "VCC_4") (pintype "power_in"))
      (node (ref "IC7") (pin "7") (pinfunction "A0_7") (pintype "input"))
      (node (ref "IC8") (pin "1") (pinfunction "V1_1") (pintype "input"))
      (node (ref "IC8") (pin "10") (pinfunction "VCC_10") (pintype "power_in"))
      (node (ref "IC8") (pin "8") (pinfunction "ADR0_8") (pintype "input"))
      (node (ref "Q2") (pin "4") (pinfunction "VCC_4") (pintype "power_in"))
      (node (ref "Q6") (pin "C") (pinfunction "C_C") (pintype "passive"))
      (node (ref "Q7") (pin "C") (pinfunction "C_C") (pintype "passive"))
      (node (ref "Q8") (pin "C") (pinfunction "C_C") (pintype "passive"))
      (node (ref "Q9") (pin "C") (pinfunction "C_C") (pintype "passive"))
      (node (ref "R1") (pin "1") (pinfunction "1_1") (pintype "passive"))
      (node (ref "R10") (pin "1") (pinfunction "1_1") (pintype "passive"))
      (node (ref "R2") (pin "1") (pinfunction "1_1") (pintype "passive"))
      (node (ref "R33") (pin "2") (pinfunction "2_2") (pintype "passive"))
      (node (ref "R34") (pin "2") (pinfunction "2_2") (pintype "passive"))
      (node (ref "R35") (pin "2") (pinfunction "2_2") (pintype "passive"))
      (node (ref "R4") (pin "1") (pinfunction "1_1") (pintype "passive"))
      (node (ref "R5") (pin "1") (pinfunction "1_1") (pintype "passive"))
      (node (ref "R6") (pin "2") (pinfunction "2_2") (pintype "passive"))
      (node (ref "R8") (pin "2") (pinfunction "2_2") (pintype "passive"))
      (node (ref "S1") (pin "1") (pinfunction "1_1") (pintype "passive"))
      (node (ref "S1") (pin "2") (pinfunction "2_2") (pintype "passive"))
    )
    (net (code "68") (name "unconnected-(IC1-ADC6-Pad19)") (class "Default")
      (node (ref "IC1") (pin "19") (pinfunction "ADC6_19") (pintype "passive"))
    )
    (net (code "69") (name "unconnected-(IC2-SC1-Pad8)") (class "Default")
      (node (ref "IC2") (pin "8") (pinfunction "SC1_8") (pintype "bidirectional"))
    )
    (net (code "70") (name "unconnected-(IC2-SD1-Pad7)") (class "Default")
      (node (ref "IC2") (pin "7") (pinfunction "SD1_7") (pintype "bidirectional"))
    )
    (net (code "71") (name "unconnected-(IC5-FAULTN-Pad6)") (class "Default")
      (node (ref "IC5") (pin "6") (pinfunction "FAULTN_6") (pintype "output"))
    )
    (net (code "72") (name "unconnected-(IC7-FAULTN-Pad6)") (class "Default")
      (node (ref "IC7") (pin "6") (pinfunction "FAULTN_6") (pintype "output"))
    )
  )
)
